# SoM.net
KiCad netlist of a schematic drawn in Altium Designer
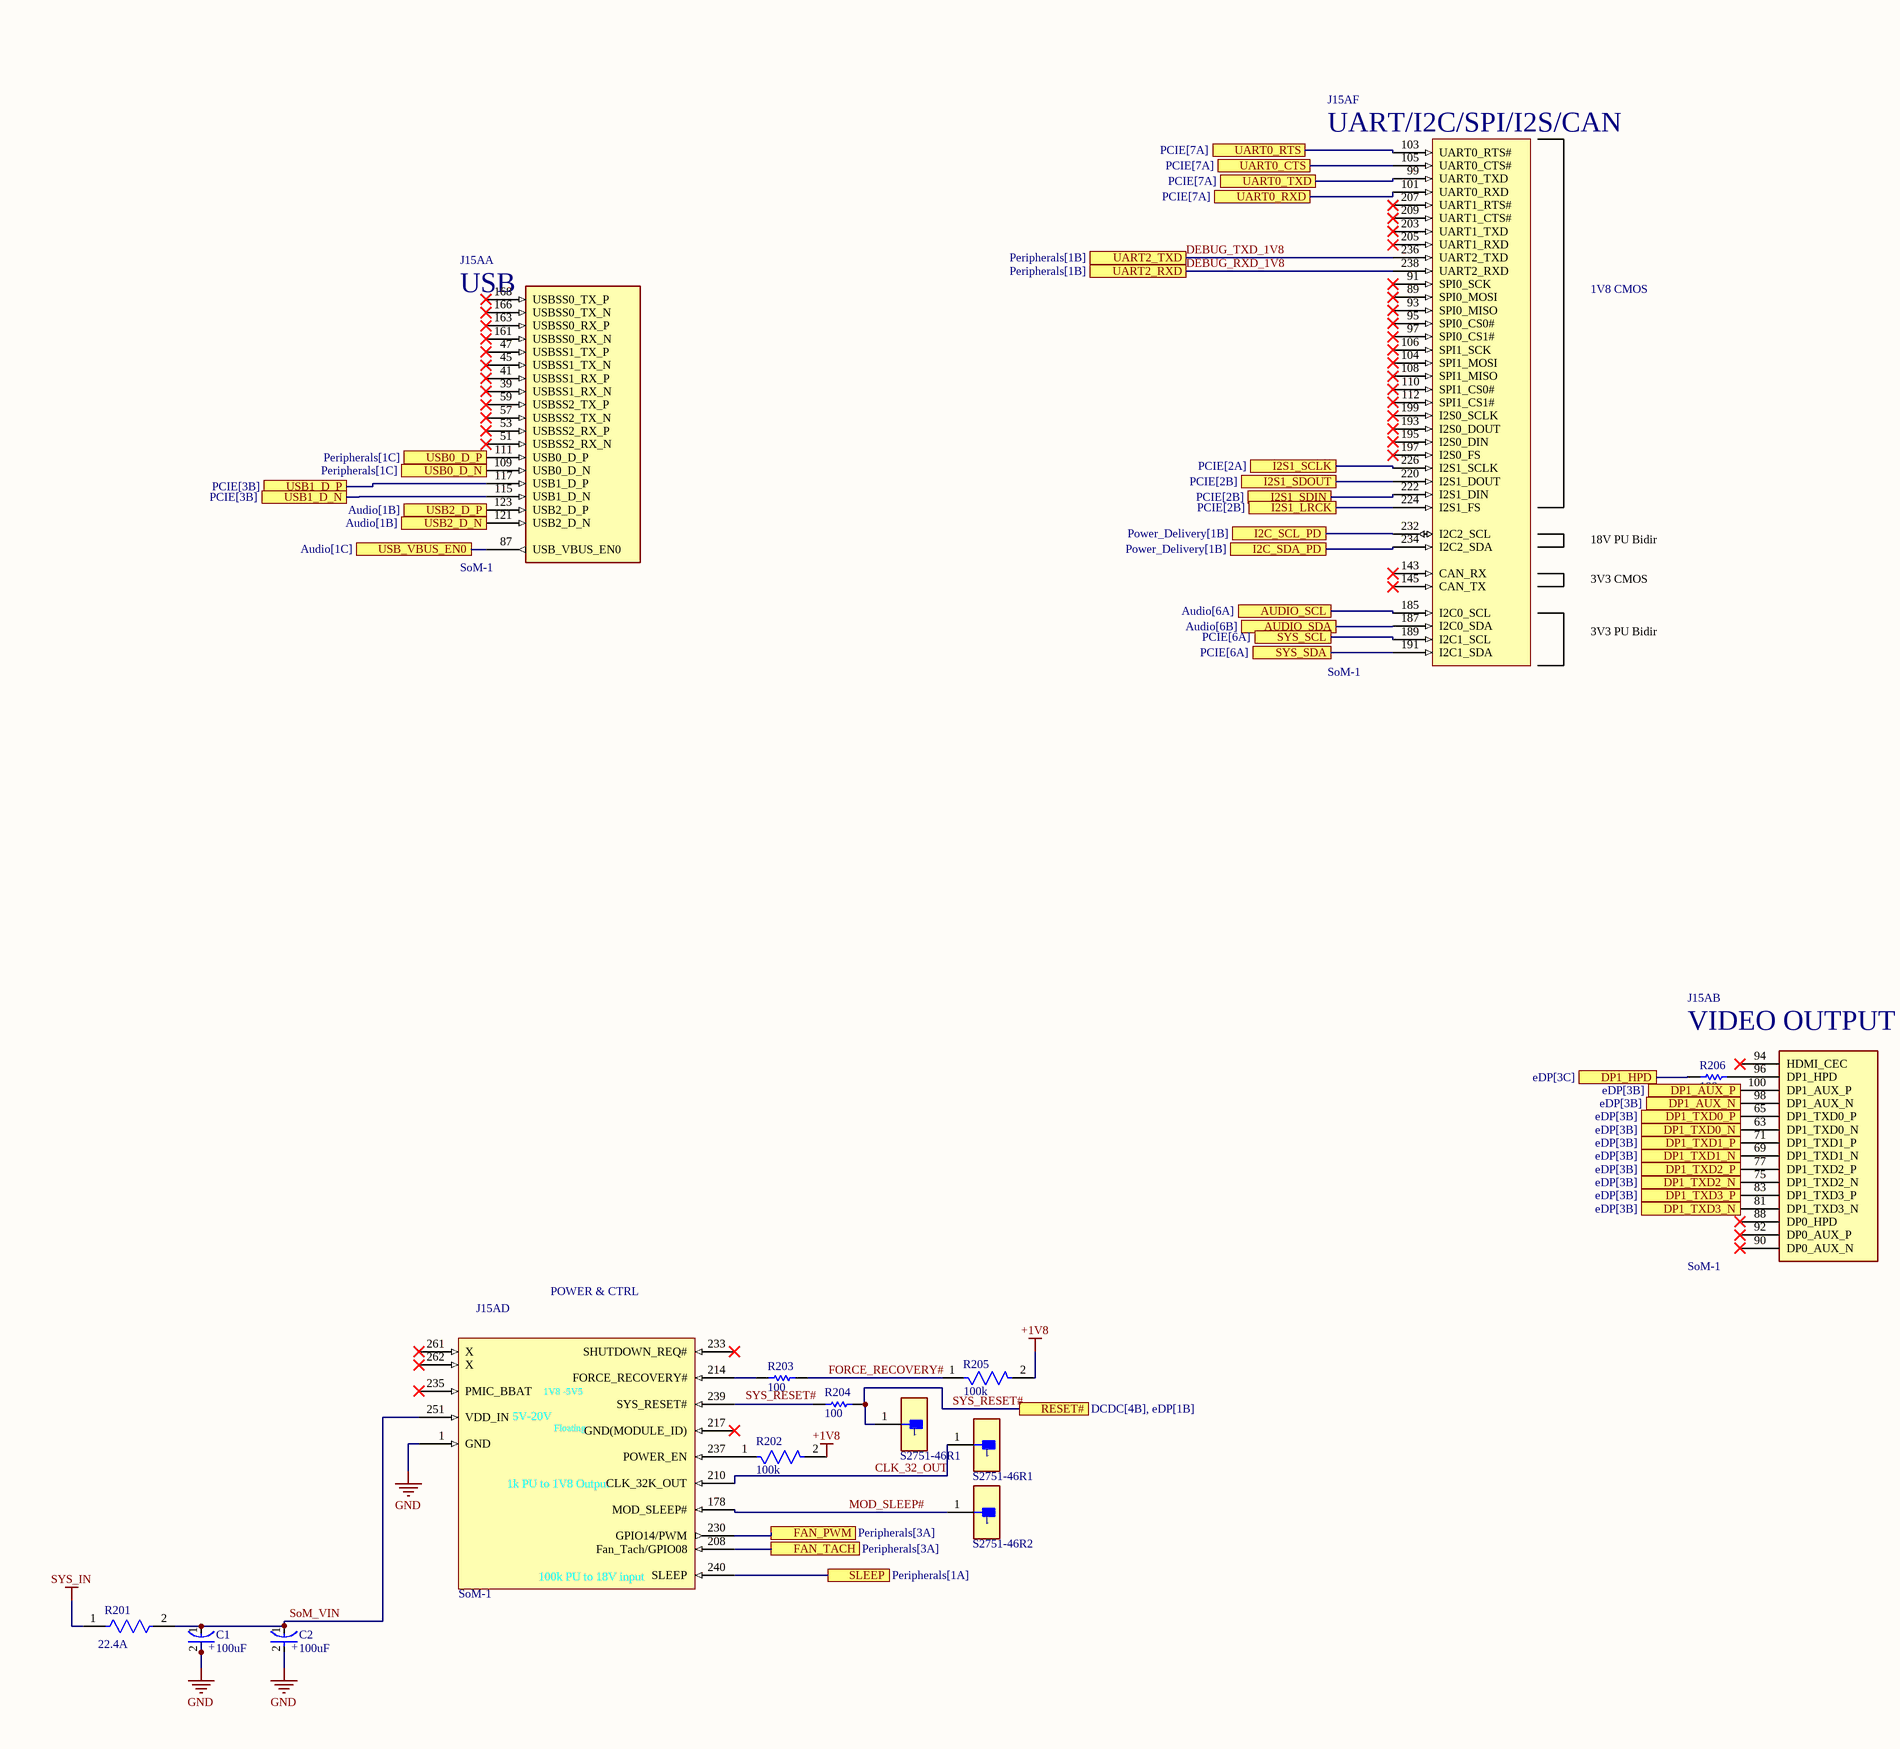
[diagram p0: SoM.SchDoc, left]
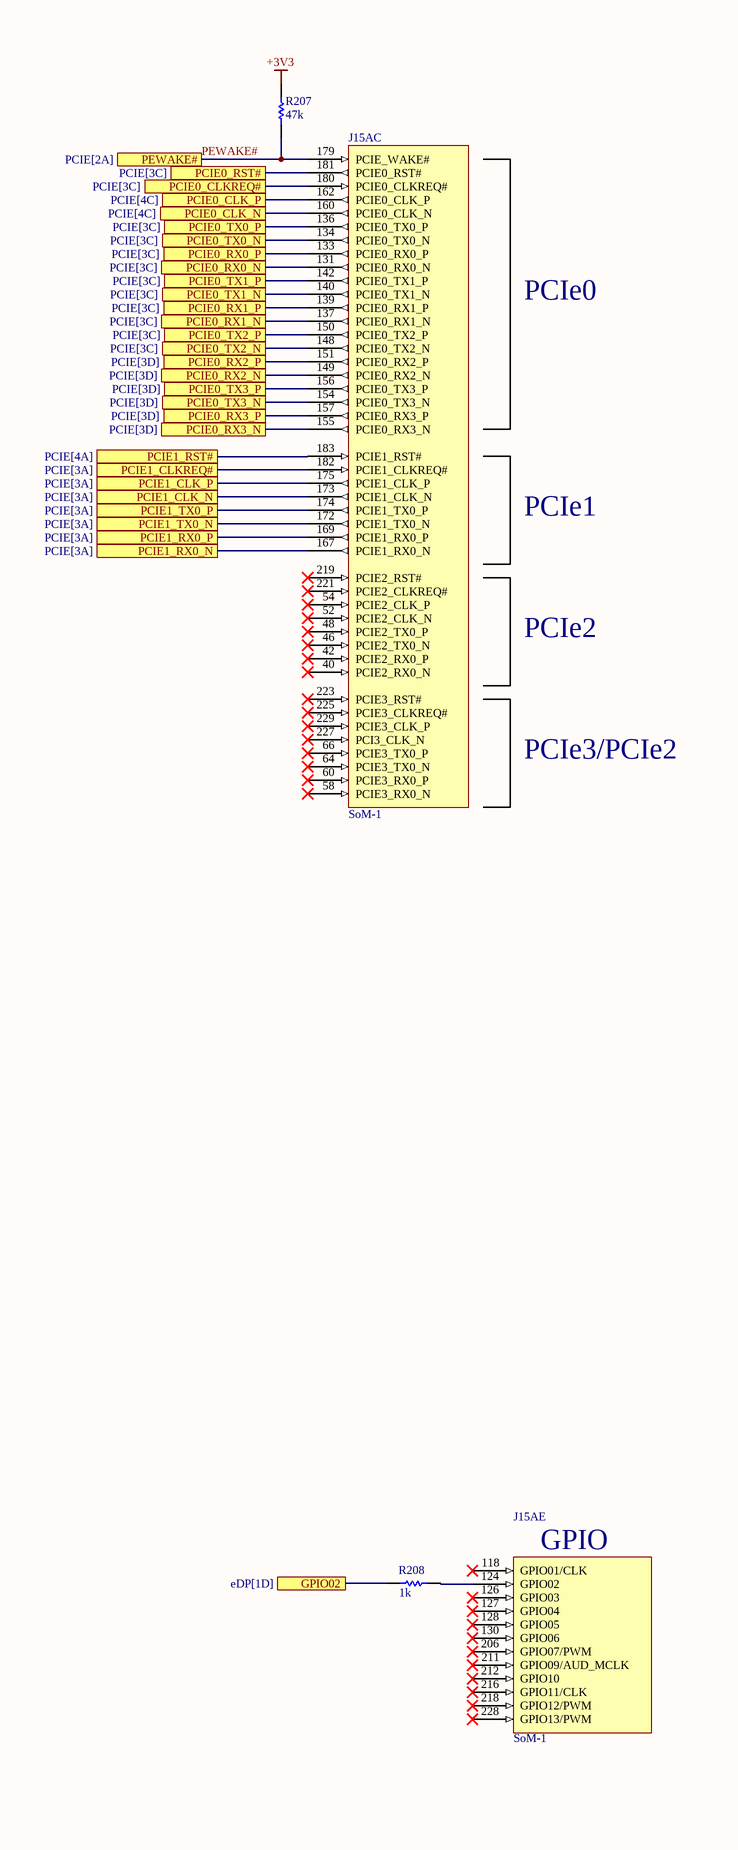
[diagram p1: SoM.SchDoc, right]

(export (version "E")
  (design (tool "Eeschema 10.0.6"))
  (components
    (comp (ref "C1")
      (value "100uF")
      (footprint "FP-T521D107M025ATE040-MFG")
      (description "CAP TANT POLY 100UF 25V 2917")
      (fields (field (name "TOLERANCE") "20%"))
      (libsource (lib "Altium Content Vault") (part "a00bbbee19879c290e62620ae7e47b1"))
    )
    (comp (ref "C2")
      (value "100uF")
      (footprint "FP-T521D107M025ATE040-MFG")
      (description "CAP TANT POLY 100UF 25V 2917")
      (fields (field (name "TOLERANCE") "20%"))
      (libsource (lib "Altium Content Vault") (part "a00bbbee19879c290e62620ae7e47b1"))
    )
    (comp (ref "J15A")
      (value "SoM-1")
      (footprint "FP-2309413-1-MFG")
      (description "Memory Card Connector, DDR4, SODIMM, Cam-In Locking, 260 Contacts, Copper Alloy")
      (fields (field (name "SOURCE") "4d1075b24ee2591bdcd47d674b3d2aa.SchLib"))
      (libsource (lib "Evan") (part "SoM"))
    )
    (comp (ref "J201")
      (value "S2751-46R1")
      (footprint "FP-S2751-46R-MFG")
      (description "PC TEST POINT NATURAL")
      (libsource (lib "Altium Content Vault") (part "dd45045ce8184df9e99e12baf3f412c"))
    )
    (comp (ref "J202")
      (value "S2751-46R1")
      (footprint "FP-S2751-46R-MFG")
      (description "PC TEST POINT NATURAL")
      (libsource (lib "Altium Content Vault") (part "dd45045ce8184df9e99e12baf3f412c"))
    )
    (comp (ref "J203")
      (value "S2751-46R2")
      (footprint "FP-S2751-46R-MFG")
      (description "PC TEST POINT NATURAL")
      (libsource (lib "Altium Content Vault") (part "dd45045ce8184df9e99e12baf3f412c"))
    )
    (comp (ref "R201")
      (value "22.4A")
      (footprint "FP-HCJ0603-MFG")
      (description "RES 0 OHM JUMPER 1/4W 0603")
      (libsource (lib "Altium Content Vault") (part "1029c3af85768c4190bb7ad29bc67b5"))
    )
    (comp (ref "R202")
      (value "100k")
      (footprint "FP-RC0402-0_4-IPC_A")
      (description "RES 100K OHM 5% 1/16W 0402")
      (fields (field (name "TOLERANCE") "5%"))
      (libsource (lib "Altium Content Vault") (part "1029c3af85768c4190bb7ad29bc67b5"))
    )
    (comp (ref "R203")
      (value "100")
      (footprint "RESC1005X40X25ML05T10")
      (fields (field (name "PART NUMBER") "RC0402FR-07100RL") (field (name "MANUFACTURER") "Yageo / Phycomp"))
      (libsource (lib "Altium Content Vault") (part "RES"))
    )
    (comp (ref "R204")
      (value "100")
      (footprint "RESC1005X40X25ML05T10")
      (fields (field (name "PART NUMBER") "RC0402FR-07100RL") (field (name "MANUFACTURER") "Yageo / Phycomp"))
      (libsource (lib "Altium Content Vault") (part "RES"))
    )
    (comp (ref "R205")
      (value "100k")
      (footprint "FP-RC0402-0_4-IPC_A")
      (description "RES 100K OHM 5% 1/16W 0402")
      (fields (field (name "TOLERANCE") "5%"))
      (libsource (lib "Altium Content Vault") (part "1029c3af85768c4190bb7ad29bc67b5"))
    )
    (comp (ref "R206")
      (value "100")
      (footprint "RESC1005X40X25ML05T10")
      (fields (field (name "PART NUMBER") "RC0402FR-07100RL") (field (name "MANUFACTURER") "Yageo / Phycomp"))
      (libsource (lib "Altium Content Vault") (part "RES"))
    )
    (comp (ref "R207")
      (value "47k")
      (footprint "RESC1005X40X25ML05T10")
      (fields (field (name "PART NUMBER") "RC0402FR-0747KL") (field (name "MANUFACTURER") "Yageo / Phycomp"))
      (libsource (lib "Altium Content Vault") (part "RES"))
    )
    (comp (ref "R208")
      (value "1k")
      (footprint "RESC3216X60X45ML15T20")
      (description "Chip Resistor, 1 KOhm, +/- 1%, 0.25 W, -55 to 155 degC, 1206 (3216 Metric), RoHS, Tape and Reel")
      (fields (field (name "MANUFACTURER") "Vishay Semiconductor") (field (name "TOLERANCE") "1%"))
      (libsource (lib "Altium Content Vault") (part "RES-2"))
    )
  )
  (nets
    (net (code "1") (name "+1V8") (class "Default")
      (node (ref "R202") (pin "2") (pinfunction "2_2") (pintype "passive"))
      (node (ref "R205") (pin "2") (pinfunction "2_2") (pintype "passive"))
    )
    (net (code "2") (name "+3V3") (class "Default")
      (node (ref "R207") (pin "2") (pinfunction "2_2") (pintype "passive"))
    )
    (net (code "3") (name "/AUDIO_SCL") (class "Default")
      (node (ref "J15A") (pin "185") (pinfunction "I2C0_SCL_185") (pintype "input"))
    )
    (net (code "4") (name "/AUDIO_SDA") (class "Default")
      (node (ref "J15A") (pin "187") (pinfunction "I2C0_SDA_187") (pintype "input"))
    )
    (net (code "5") (name "/CLK_32_OUT") (class "Default")
      (node (ref "J15A") (pin "210") (pinfunction "CLK_32K_OUT_210") (pintype "input"))
      (node (ref "J202") (pin "1") (pinfunction "1_1") (pintype "passive"))
    )
    (net (code "6") (name "/DEBUG_RXD_1V8") (class "Default")
      (node (ref "J15A") (pin "238") (pinfunction "UART2_RXD_238") (pintype "input"))
    )
    (net (code "7") (name "/DEBUG_TXD_1V8") (class "Default")
      (node (ref "J15A") (pin "236") (pinfunction "UART2_TXD_236") (pintype "input"))
    )
    (net (code "8") (name "/DP1_AUX_N") (class "Default")
      (node (ref "J15A") (pin "98") (pinfunction "DP1_AUX_N_98") (pintype "passive"))
    )
    (net (code "9") (name "/DP1_AUX_P") (class "Default")
      (node (ref "J15A") (pin "100") (pinfunction "DP1_AUX_P_100") (pintype "passive"))
    )
    (net (code "10") (name "/DP1_HPD") (class "Default")
      (node (ref "R206") (pin "1") (pinfunction "1_1") (pintype "passive"))
    )
    (net (code "11") (name "/DP1_TXD0_N") (class "Default")
      (node (ref "J15A") (pin "63") (pinfunction "DP1_TXD0_N_63") (pintype "passive"))
    )
    (net (code "12") (name "/DP1_TXD0_P") (class "Default")
      (node (ref "J15A") (pin "65") (pinfunction "DP1_TXD0_P_65") (pintype "passive"))
    )
    (net (code "13") (name "/DP1_TXD1_N") (class "Default")
      (node (ref "J15A") (pin "69") (pinfunction "DP1_TXD1_N_69") (pintype "passive"))
    )
    (net (code "14") (name "/DP1_TXD1_P") (class "Default")
      (node (ref "J15A") (pin "71") (pinfunction "DP1_TXD1_P_71") (pintype "passive"))
    )
    (net (code "15") (name "/DP1_TXD2_N") (class "Default")
      (node (ref "J15A") (pin "75") (pinfunction "DP1_TXD2_N_75") (pintype "passive"))
    )
    (net (code "16") (name "/DP1_TXD2_P") (class "Default")
      (node (ref "J15A") (pin "77") (pinfunction "DP1_TXD2_P_77") (pintype "passive"))
    )
    (net (code "17") (name "/DP1_TXD3_N") (class "Default")
      (node (ref "J15A") (pin "81") (pinfunction "DP1_TXD3_N_81") (pintype "passive"))
    )
    (net (code "18") (name "/DP1_TXD3_P") (class "Default")
      (node (ref "J15A") (pin "83") (pinfunction "DP1_TXD3_P_83") (pintype "passive"))
    )
    (net (code "19") (name "/FAN_PWM") (class "Default")
      (node (ref "J15A") (pin "230") (pinfunction "GPIO14/PWM_230") (pintype "output"))
    )
    (net (code "20") (name "/FAN_TACH") (class "Default")
      (node (ref "J15A") (pin "208") (pinfunction "Fan_Tach/GPIO08_208") (pintype "input"))
    )
    (net (code "22") (name "/GPIO02") (class "Default")
      (node (ref "R208") (pin "2") (pinfunction "2_2") (pintype "passive"))
    )
    (net (code "23") (name "/I2C_SCL_PD") (class "Default")
      (node (ref "J15A") (pin "232") (pinfunction "I2C2_SCL_232") (pintype "input"))
    )
    (net (code "24") (name "/I2C_SDA_PD") (class "Default")
      (node (ref "J15A") (pin "234") (pinfunction "I2C2_SDA_234") (pintype "input"))
    )
    (net (code "25") (name "/I2S1_LRCK") (class "Default")
      (node (ref "J15A") (pin "224") (pinfunction "I2S1_FS_224") (pintype "input"))
    )
    (net (code "26") (name "/I2S1_SCLK") (class "Default")
      (node (ref "J15A") (pin "226") (pinfunction "I2S1_SCLK_226") (pintype "input"))
    )
    (net (code "27") (name "/I2S1_SDIN") (class "Default")
      (node (ref "J15A") (pin "222") (pinfunction "I2S1_DIN_222") (pintype "input"))
    )
    (net (code "28") (name "/I2S1_SDOUT") (class "Default")
      (node (ref "J15A") (pin "220") (pinfunction "I2S1_DOUT_220") (pintype "input"))
    )
    (net (code "29") (name "/MOD_SLEEP#") (class "Default")
      (node (ref "J15A") (pin "178") (pinfunction "MOD_SLEEP#_178") (pintype "input"))
      (node (ref "J203") (pin "1") (pinfunction "1_1") (pintype "passive"))
    )
    (net (code "30") (name "/PCIE0_CLKREQ#") (class "Default")
      (node (ref "J15A") (pin "180") (pinfunction "PCIE0_CLKREQ#_180") (pintype "input"))
    )
    (net (code "31") (name "/PCIE0_CLK_N") (class "Default")
      (node (ref "J15A") (pin "160") (pinfunction "PCIE0_CLK_N_160") (pintype "input"))
    )
    (net (code "32") (name "/PCIE0_CLK_P") (class "Default")
      (node (ref "J15A") (pin "162") (pinfunction "PCIE0_CLK_P_162") (pintype "input"))
    )
    (net (code "33") (name "/PCIE0_RST#") (class "Default")
      (node (ref "J15A") (pin "181") (pinfunction "PCIE2_CLKREQ#_181") (pintype "input"))
    )
    (net (code "34") (name "/PCIE0_RX0_N") (class "Default")
      (node (ref "J15A") (pin "131") (pinfunction "PCIE0_RX0_N_131") (pintype "input"))
    )
    (net (code "35") (name "/PCIE0_RX0_P") (class "Default")
      (node (ref "J15A") (pin "133") (pinfunction "PCIE0_RX0_P_133") (pintype "input"))
    )
    (net (code "36") (name "/PCIE0_RX1_N") (class "Default")
      (node (ref "J15A") (pin "137") (pinfunction "PCIE0_RX1_N_137") (pintype "input"))
    )
    (net (code "37") (name "/PCIE0_RX1_P") (class "Default")
      (node (ref "J15A") (pin "139") (pinfunction "PCIE0_RX1_P_139") (pintype "input"))
    )
    (net (code "38") (name "/PCIE0_RX2_N") (class "Default")
      (node (ref "J15A") (pin "149") (pinfunction "PCIE0_RX2_N_149") (pintype "input"))
    )
    (net (code "39") (name "/PCIE0_RX2_P") (class "Default")
      (node (ref "J15A") (pin "151") (pinfunction "PCIE0_RX2_P_151") (pintype "input"))
    )
    (net (code "40") (name "/PCIE0_RX3_N") (class "Default")
      (node (ref "J15A") (pin "155") (pinfunction "PCIE0_RX3_N_155") (pintype "input"))
    )
    (net (code "41") (name "/PCIE0_RX3_P") (class "Default")
      (node (ref "J15A") (pin "157") (pinfunction "PCIE0_RX3_P_157") (pintype "input"))
    )
    (net (code "42") (name "/PCIE0_TX0_N") (class "Default")
      (node (ref "J15A") (pin "134") (pinfunction "PCIE0_TX0_N_134") (pintype "input"))
    )
    (net (code "43") (name "/PCIE0_TX0_P") (class "Default")
      (node (ref "J15A") (pin "136") (pinfunction "PCIE0_TX0_P_136") (pintype "input"))
    )
    (net (code "44") (name "/PCIE0_TX1_N") (class "Default")
      (node (ref "J15A") (pin "140") (pinfunction "PCIE0_TX1_N_140") (pintype "input"))
    )
    (net (code "45") (name "/PCIE0_TX1_P") (class "Default")
      (node (ref "J15A") (pin "142") (pinfunction "PCIE0_TX1_P_142") (pintype "input"))
    )
    (net (code "46") (name "/PCIE0_TX2_N") (class "Default")
      (node (ref "J15A") (pin "148") (pinfunction "PCIE0_TX2_N_148") (pintype "input"))
    )
    (net (code "47") (name "/PCIE0_TX2_P") (class "Default")
      (node (ref "J15A") (pin "150") (pinfunction "PCIE0_TX2_P_150") (pintype "input"))
    )
    (net (code "48") (name "/PCIE0_TX3_N") (class "Default")
      (node (ref "J15A") (pin "154") (pinfunction "PCIE0_TX3_P_154") (pintype "input"))
    )
    (net (code "49") (name "/PCIE0_TX3_P") (class "Default")
      (node (ref "J15A") (pin "156") (pinfunction "PCIE0_TX3_P_156") (pintype "input"))
    )
    (net (code "50") (name "/PCIE1_CLKREQ#") (class "Default")
      (node (ref "J15A") (pin "182") (pinfunction "PCIE1_CLKREQ#_182") (pintype "input"))
    )
    (net (code "51") (name "/PCIE1_CLK_N") (class "Default")
      (node (ref "J15A") (pin "173") (pinfunction "PCIE1_CLK_N_173") (pintype "input"))
    )
    (net (code "52") (name "/PCIE1_CLK_P") (class "Default")
      (node (ref "J15A") (pin "175") (pinfunction "PCIE1_CLK_P_175") (pintype "input"))
    )
    (net (code "53") (name "/PCIE1_RST#") (class "Default")
      (node (ref "J15A") (pin "183") (pinfunction "PCIE1_RST#_183") (pintype "input"))
    )
    (net (code "54") (name "/PCIE1_RX0_N") (class "Default")
      (node (ref "J15A") (pin "167") (pinfunction "PCIE1_RX0_N_167") (pintype "input"))
    )
    (net (code "55") (name "/PCIE1_RX0_P") (class "Default")
      (node (ref "J15A") (pin "169") (pinfunction "PCIE1_RX0_P_169") (pintype "input"))
    )
    (net (code "56") (name "/PCIE1_TX0_N") (class "Default")
      (node (ref "J15A") (pin "172") (pinfunction "PCIE1_TX0_N_172") (pintype "input"))
    )
    (net (code "57") (name "/PCIE1_TX0_P") (class "Default")
      (node (ref "J15A") (pin "174") (pinfunction "PCIE1_TX0_P_174") (pintype "input"))
    )
    (net (code "58") (name "/PEWAKE#") (class "Default")
      (node (ref "J15A") (pin "179") (pinfunction "PCIE_WAKE#_179") (pintype "input"))
      (node (ref "R207") (pin "1") (pinfunction "1_1") (pintype "passive"))
    )
    (net (code "59") (name "/SLEEP") (class "Default")
      (node (ref "J15A") (pin "240") (pinfunction "SLEEP_240") (pintype "input"))
    )
    (net (code "60") (name "/SYS_RESET#") (class "Default")
      (node (ref "J201") (pin "1") (pinfunction "1_1") (pintype "passive"))
      (node (ref "R204") (pin "2") (pinfunction "2_2") (pintype "passive"))
    )
    (net (code "61") (name "/SYS_SCL") (class "Default")
      (node (ref "J15A") (pin "189") (pinfunction "IS2C1_SCL_189") (pintype "input"))
    )
    (net (code "62") (name "/SYS_SDA") (class "Default")
      (node (ref "J15A") (pin "191") (pinfunction "IS2C1_SDA_191") (pintype "input"))
    )
    (net (code "63") (name "/SoM_VIN") (class "Default")
      (node (ref "C1") (pin "1") (pinfunction "C_1") (pintype "passive"))
      (node (ref "C2") (pin "1") (pinfunction "C_1") (pintype "passive"))
      (node (ref "J15A") (pin "251") (pinfunction "VDD_IN_251") (pintype "input"))
      (node (ref "R201") (pin "2") (pinfunction "2_2") (pintype "passive"))
    )
    (net (code "64") (name "/UART0_CTS") (class "Default")
      (node (ref "J15A") (pin "105") (pinfunction "UART0_CTS#_105") (pintype "input"))
    )
    (net (code "65") (name "/UART0_RTS") (class "Default")
      (node (ref "J15A") (pin "103") (pinfunction "UART0_RTS#_103") (pintype "input"))
    )
    (net (code "66") (name "/UART0_RXD") (class "Default")
      (node (ref "J15A") (pin "101") (pinfunction "UART0_RXD_101") (pintype "input"))
    )
    (net (code "67") (name "/UART0_TXD") (class "Default")
      (node (ref "J15A") (pin "99") (pinfunction "UART0_TXD_99") (pintype "input"))
    )
    (net (code "68") (name "/USB0_D_N") (class "Default")
      (node (ref "J15A") (pin "109") (pinfunction "USB0_D_N_109") (pintype "input"))
    )
    (net (code "69") (name "/USB0_D_P") (class "Default")
      (node (ref "J15A") (pin "111") (pinfunction "USB0_D_P_111") (pintype "input"))
    )
    (net (code "70") (name "/USB1_D_N") (class "Default")
      (node (ref "J15A") (pin "115") (pinfunction "USB1_D_N_115") (pintype "input"))
    )
    (net (code "71") (name "/USB1_D_P") (class "Default")
      (node (ref "J15A") (pin "117") (pinfunction "USB1_D_P_117") (pintype "input"))
    )
    (net (code "72") (name "/USB2_D_N") (class "Default")
      (node (ref "J15A") (pin "121") (pinfunction "USB2_D_N_121") (pintype "input"))
    )
    (net (code "73") (name "/USB2_D_P") (class "Default")
      (node (ref "J15A") (pin "123") (pinfunction "USB2_D_P_123") (pintype "input"))
    )
    (net (code "74") (name "/USB_VBUS_EN0") (class "Default")
      (node (ref "J15A") (pin "87") (pinfunction "USB_VBUS_EN0_87") (pintype "input"))
    )
    (net (code "75") (name "GND") (class "Default")
      (node (ref "C1") (pin "2") (pinfunction "A_2") (pintype "passive"))
      (node (ref "C2") (pin "2") (pinfunction "A_2") (pintype "passive"))
      (node (ref "J15A") (pin "1") (pinfunction "GND_1") (pintype "input"))
    )
    (net (code "76") (name "Net-(J15AB-DP1_HPD)") (class "Default")
      (node (ref "J15A") (pin "96") (pinfunction "DP1_HPD_96") (pintype "passive"))
      (node (ref "R206") (pin "2") (pinfunction "2_2") (pintype "passive"))
    )
    (net (code "77") (name "Net-(J15AD-FORCE_RECOVERY#)") (class "Default")
      (node (ref "J15A") (pin "214") (pinfunction "FORCE_RECOVERY#_214") (pintype "input"))
      (node (ref "R203") (pin "1") (pinfunction "1_1") (pintype "passive"))
    )
    (net (code "78") (name "Net-(J15AD-POWER_EN)") (class "Default")
      (node (ref "J15A") (pin "237") (pinfunction "POWER_EN_237") (pintype "input"))
      (node (ref "R202") (pin "1") (pinfunction "1_1") (pintype "passive"))
    )
    (net (code "79") (name "Net-(J15AD-SYS_RESET#)") (class "Default")
      (node (ref "J15A") (pin "239") (pinfunction "SYS_RESET#_239") (pintype "input"))
      (node (ref "R204") (pin "1") (pinfunction "1_1") (pintype "passive"))
    )
    (net (code "80") (name "Net-(J15AE-GPIO02)") (class "Default")
      (node (ref "J15A") (pin "124") (pinfunction "GPIO02_124") (pintype "input"))
      (node (ref "R208") (pin "1") (pinfunction "1_1") (pintype "passive"))
    )
    (net (code "81") (name "Net-(R203-Pad2)") (class "Default")
      (node (ref "R203") (pin "2") (pinfunction "2_2") (pintype "passive"))
      (node (ref "R205") (pin "1") (pinfunction "1_1") (pintype "passive"))
    )
    (net (code "82") (name "SYS_IN") (class "Default")
      (node (ref "R201") (pin "1") (pinfunction "1_1") (pintype "passive"))
    )
    (net (code "83") (name "unconnected-(J15AA-USBSS0_RX_N-Pad161)") (class "Default")
      (node (ref "J15A") (pin "161") (pinfunction "USBSS0_RX_N_161") (pintype "input+no_connect"))
    )
    (net (code "84") (name "unconnected-(J15AA-USBSS0_RX_P-Pad163)") (class "Default")
      (node (ref "J15A") (pin "163") (pinfunction "USBSS0_RX_P_163") (pintype "input+no_connect"))
    )
    (net (code "85") (name "unconnected-(J15AA-USBSS0_TX_N-Pad166)") (class "Default")
      (node (ref "J15A") (pin "166") (pinfunction "USBSS0_TX_N_166") (pintype "input+no_connect"))
    )
    (net (code "86") (name "unconnected-(J15AA-USBSS0_TX_P-Pad168)") (class "Default")
      (node (ref "J15A") (pin "168") (pinfunction "USBSS0_TX_P_168") (pintype "input+no_connect"))
    )
    (net (code "87") (name "unconnected-(J15AA-USBSS1_RX_N-Pad39)") (class "Default")
      (node (ref "J15A") (pin "39") (pinfunction "USBSS1_RX_N_39") (pintype "input+no_connect"))
    )
    (net (code "88") (name "unconnected-(J15AA-USBSS1_RX_P-Pad41)") (class "Default")
      (node (ref "J15A") (pin "41") (pinfunction "USBSS1_RX_P_41") (pintype "input+no_connect"))
    )
    (net (code "89") (name "unconnected-(J15AA-USBSS1_TX_N-Pad45)") (class "Default")
      (node (ref "J15A") (pin "45") (pinfunction "USBSS1_TX_N_45") (pintype "input+no_connect"))
    )
    (net (code "90") (name "unconnected-(J15AA-USBSS1_TX_P-Pad47)") (class "Default")
      (node (ref "J15A") (pin "47") (pinfunction "USBSS1_TX_P_47") (pintype "input+no_connect"))
    )
    (net (code "91") (name "unconnected-(J15AA-USBSS2_RX_N-Pad51)") (class "Default")
      (node (ref "J15A") (pin "51") (pinfunction "USBSS2_RX_N_51") (pintype "input+no_connect"))
    )
    (net (code "92") (name "unconnected-(J15AA-USBSS2_RX_P-Pad53)") (class "Default")
      (node (ref "J15A") (pin "53") (pinfunction "USBSS2_RX_P_53") (pintype "input+no_connect"))
    )
    (net (code "93") (name "unconnected-(J15AA-USBSS2_TX_N-Pad57)") (class "Default")
      (node (ref "J15A") (pin "57") (pinfunction "USBSS2_TX_N_57") (pintype "input+no_connect"))
    )
    (net (code "94") (name "unconnected-(J15AA-USBSS2_TX_P-Pad59)") (class "Default")
      (node (ref "J15A") (pin "59") (pinfunction "USBSS2_TX_P_59") (pintype "input+no_connect"))
    )
    (net (code "95") (name "unconnected-(J15AB-DP0_AUX_N-Pad90)") (class "Default")
      (node (ref "J15A") (pin "90") (pinfunction "DP0_AUX_N_90") (pintype "passive+no_connect"))
    )
    (net (code "96") (name "unconnected-(J15AB-DP0_AUX_P-Pad92)") (class "Default")
      (node (ref "J15A") (pin "92") (pinfunction "DP0_AUX_P_92") (pintype "passive+no_connect"))
    )
    (net (code "97") (name "unconnected-(J15AB-DP0_HPD-Pad88)") (class "Default")
      (node (ref "J15A") (pin "88") (pinfunction "DP0_HPD_88") (pintype "passive+no_connect"))
    )
    (net (code "98") (name "unconnected-(J15AB-HDMI_CEC-Pad94)") (class "Default")
      (node (ref "J15A") (pin "94") (pinfunction "HDMI_CEC_94") (pintype "passive+no_connect"))
    )
    (net (code "99") (name "unconnected-(J15AC-PCI3_CLK_N-Pad227)") (class "Default")
      (node (ref "J15A") (pin "227") (pinfunction "PCI3_CLK_N_227") (pintype "input+no_connect"))
    )
    (net (code "100") (name "unconnected-(J15AC-PCIE2_CLKREQ#-Pad221)") (class "Default")
      (node (ref "J15A") (pin "221") (pinfunction "PCIE2_CLKREQ#_221") (pintype "input+no_connect"))
    )
    (net (code "101") (name "unconnected-(J15AC-PCIE2_CLK_N-Pad52)") (class "Default")
      (node (ref "J15A") (pin "52") (pinfunction "PCIE2_CLK_N_52") (pintype "input+no_connect"))
    )
    (net (code "102") (name "unconnected-(J15AC-PCIE2_CLK_P-Pad54)") (class "Default")
      (node (ref "J15A") (pin "54") (pinfunction "PCIE2_CLK_P_54") (pintype "input+no_connect"))
    )
    (net (code "103") (name "unconnected-(J15AC-PCIE2_RST#-Pad219)") (class "Default")
      (node (ref "J15A") (pin "219") (pinfunction "PCIE2_RST#_219") (pintype "input+no_connect"))
    )
    (net (code "104") (name "unconnected-(J15AC-PCIE2_RX0_N-Pad40)") (class "Default")
      (node (ref "J15A") (pin "40") (pinfunction "PCIE2_RX0_N_40") (pintype "input+no_connect"))
    )
    (net (code "105") (name "unconnected-(J15AC-PCIE2_RX0_P-Pad42)") (class "Default")
      (node (ref "J15A") (pin "42") (pinfunction "PCIE2_RX0_P_42") (pintype "input+no_connect"))
    )
    (net (code "106") (name "unconnected-(J15AC-PCIE2_TX0_N-Pad46)") (class "Default")
      (node (ref "J15A") (pin "46") (pinfunction "PCIE2_TX0_N_46") (pintype "input+no_connect"))
    )
    (net (code "107") (name "unconnected-(J15AC-PCIE2_TX0_P-Pad48)") (class "Default")
      (node (ref "J15A") (pin "48") (pinfunction "PCIE2_TX0_P_48") (pintype "input+no_connect"))
    )
    (net (code "108") (name "unconnected-(J15AC-PCIE3_CLKREQ#-Pad225)") (class "Default")
      (node (ref "J15A") (pin "225") (pinfunction "PCIE3_CLKREQ#_225") (pintype "input+no_connect"))
    )
    (net (code "109") (name "unconnected-(J15AC-PCIE3_CLK_P-Pad229)") (class "Default")
      (node (ref "J15A") (pin "229") (pinfunction "PCIE3_CLK_P_229") (pintype "input+no_connect"))
    )
    (net (code "110") (name "unconnected-(J15AC-PCIE3_RST#-Pad223)") (class "Default")
      (node (ref "J15A") (pin "223") (pinfunction "PCIE3_RST#_223") (pintype "input+no_connect"))
    )
    (net (code "111") (name "unconnected-(J15AC-PCIE3_RX0_N-Pad58)") (class "Default")
      (node (ref "J15A") (pin "58") (pinfunction "PCIE3_RX0_N_58") (pintype "input+no_connect"))
    )
    (net (code "112") (name "unconnected-(J15AC-PCIE3_RX0_P-Pad60)") (class "Default")
      (node (ref "J15A") (pin "60") (pinfunction "PCIE3_RX0_P_60") (pintype "input+no_connect"))
    )
    (net (code "113") (name "unconnected-(J15AC-PCIE3_TX0_N-Pad64)") (class "Default")
      (node (ref "J15A") (pin "64") (pinfunction "PCIE3_TX0_N_64") (pintype "input+no_connect"))
    )
    (net (code "114") (name "unconnected-(J15AC-PCIE3_TX0_P-Pad66)") (class "Default")
      (node (ref "J15A") (pin "66") (pinfunction "PCIE3_TX0_P_66") (pintype "input+no_connect"))
    )
    (net (code "115") (name "unconnected-(J15AD-GND(MODULE_ID)-Pad217)") (class "Default")
      (node (ref "J15A") (pin "217") (pinfunction "GND(MODULE_ID)_217") (pintype "input+no_connect"))
    )
    (net (code "116") (name "unconnected-(J15AD-PMIC_BBAT-Pad235)") (class "Default")
      (node (ref "J15A") (pin "235") (pinfunction "PMIC_BBAT_235") (pintype "input+no_connect"))
    )
    (net (code "117") (name "unconnected-(J15AD-SHUTDOWN_REQ#-Pad233)") (class "Default")
      (node (ref "J15A") (pin "233") (pinfunction "SHUTDOWN_REQ#_233") (pintype "input+no_connect"))
    )
    (net (code "118") (name "unconnected-(J15AD-X-Pad261)") (class "Default")
      (node (ref "J15A") (pin "261") (pinfunction "X_261") (pintype "input+no_connect"))
    )
    (net (code "119") (name "unconnected-(J15AD-X-Pad262)") (class "Default")
      (node (ref "J15A") (pin "262") (pinfunction "X_262") (pintype "input+no_connect"))
    )
    (net (code "120") (name "unconnected-(J15AE-GPIO01{slash}CLK-Pad118)") (class "Default")
      (node (ref "J15A") (pin "118") (pinfunction "GPIO01/CLK_118") (pintype "input+no_connect"))
    )
    (net (code "121") (name "unconnected-(J15AE-GPIO03-Pad126)") (class "Default")
      (node (ref "J15A") (pin "126") (pinfunction "GPIO03_126") (pintype "input+no_connect"))
    )
    (net (code "122") (name "unconnected-(J15AE-GPIO04-Pad127)") (class "Default")
      (node (ref "J15A") (pin "127") (pinfunction "GPIO04_127") (pintype "input+no_connect"))
    )
    (net (code "123") (name "unconnected-(J15AE-GPIO05-Pad128)") (class "Default")
      (node (ref "J15A") (pin "128") (pinfunction "GPIO05_128") (pintype "input+no_connect"))
    )
    (net (code "124") (name "unconnected-(J15AE-GPIO06-Pad130)") (class "Default")
      (node (ref "J15A") (pin "130") (pinfunction "GPIO06_130") (pintype "input+no_connect"))
    )
    (net (code "125") (name "unconnected-(J15AE-GPIO07{slash}PWM-Pad206)") (class "Default")
      (node (ref "J15A") (pin "206") (pinfunction "GPIO07/PWM_206") (pintype "input+no_connect"))
    )
    (net (code "126") (name "unconnected-(J15AE-GPIO09{slash}AUD_MCLK-Pad211)") (class "Default")
      (node (ref "J15A") (pin "211") (pinfunction "GPIO09/AUD_MCLK_211") (pintype "input+no_connect"))
    )
    (net (code "127") (name "unconnected-(J15AE-GPIO10-Pad212)") (class "Default")
      (node (ref "J15A") (pin "212") (pinfunction "GPIO10_212") (pintype "input+no_connect"))
    )
    (net (code "128") (name "unconnected-(J15AE-GPIO11{slash}CLK-Pad216)") (class "Default")
      (node (ref "J15A") (pin "216") (pinfunction "GPIO11/CLK_216") (pintype "input+no_connect"))
    )
    (net (code "129") (name "unconnected-(J15AE-GPIO12{slash}PWM-Pad218)") (class "Default")
      (node (ref "J15A") (pin "218") (pinfunction "GPIO12/PWM_218") (pintype "input+no_connect"))
    )
    (net (code "130") (name "unconnected-(J15AE-GPIO13{slash}PWM-Pad228)") (class "Default")
      (node (ref "J15A") (pin "228") (pinfunction "GPIO13/PWM_228") (pintype "input+no_connect"))
    )
    (net (code "131") (name "unconnected-(J15AF-CAN_RX-Pad143)") (class "Default")
      (node (ref "J15A") (pin "143") (pinfunction "CAN_RX_143") (pintype "input+no_connect"))
    )
    (net (code "132") (name "unconnected-(J15AF-CAN_TX-Pad145)") (class "Default")
      (node (ref "J15A") (pin "145") (pinfunction "CAN_TX_145") (pintype "input+no_connect"))
    )
    (net (code "133") (name "unconnected-(J15AF-I2S0_DIN-Pad195)") (class "Default")
      (node (ref "J15A") (pin "195") (pinfunction "I2S0_DIN_195") (pintype "input+no_connect"))
    )
    (net (code "134") (name "unconnected-(J15AF-I2S0_DOUT-Pad193)") (class "Default")
      (node (ref "J15A") (pin "193") (pinfunction "I2S0_DOUT_193") (pintype "input+no_connect"))
    )
    (net (code "135") (name "unconnected-(J15AF-I2S0_FS-Pad197)") (class "Default")
      (node (ref "J15A") (pin "197") (pinfunction "I2S0_FS_197") (pintype "input+no_connect"))
    )
    (net (code "136") (name "unconnected-(J15AF-I2S0_SCLK-Pad199)") (class "Default")
      (node (ref "J15A") (pin "199") (pinfunction "I2S0_SCLK_199") (pintype "input+no_connect"))
    )
    (net (code "137") (name "unconnected-(J15AF-SPI0_CS0#-Pad95)") (class "Default")
      (node (ref "J15A") (pin "95") (pinfunction "SPI0_CS0#_95") (pintype "input+no_connect"))
    )
    (net (code "138") (name "unconnected-(J15AF-SPI0_CS1#-Pad97)") (class "Default")
      (node (ref "J15A") (pin "97") (pinfunction "SPI0_CS1#_97") (pintype "input+no_connect"))
    )
    (net (code "139") (name "unconnected-(J15AF-SPI0_MISO-Pad93)") (class "Default")
      (node (ref "J15A") (pin "93") (pinfunction "SPI0_MISO_93") (pintype "input+no_connect"))
    )
    (net (code "140") (name "unconnected-(J15AF-SPI0_MOSI-Pad89)") (class "Default")
      (node (ref "J15A") (pin "89") (pinfunction "SPI0_MOSI_89") (pintype "input+no_connect"))
    )
    (net (code "141") (name "unconnected-(J15AF-SPI0_SCK-Pad91)") (class "Default")
      (node (ref "J15A") (pin "91") (pinfunction "SPI0_SCK_91") (pintype "input+no_connect"))
    )
    (net (code "142") (name "unconnected-(J15AF-SPI1_CS0#-Pad110)") (class "Default")
      (node (ref "J15A") (pin "110") (pinfunction "SPI1_CS0#_110") (pintype "input+no_connect"))
    )
    (net (code "143") (name "unconnected-(J15AF-SPI1_CS1#-Pad112)") (class "Default")
      (node (ref "J15A") (pin "112") (pinfunction "SPI1_CS1#_112") (pintype "input+no_connect"))
    )
    (net (code "144") (name "unconnected-(J15AF-SPI1_MISO-Pad108)") (class "Default")
      (node (ref "J15A") (pin "108") (pinfunction "SPI1_MISO_108") (pintype "input+no_connect"))
    )
    (net (code "145") (name "unconnected-(J15AF-SPI1_MOSI-Pad104)") (class "Default")
      (node (ref "J15A") (pin "104") (pinfunction "SPI1_MOSI_104") (pintype "input+no_connect"))
    )
    (net (code "146") (name "unconnected-(J15AF-SPI1_SCK-Pad106)") (class "Default")
      (node (ref "J15A") (pin "106") (pinfunction "SPI1_SCK_106") (pintype "input+no_connect"))
    )
    (net (code "147") (name "unconnected-(J15AF-UART1_CTS#-Pad209)") (class "Default")
      (node (ref "J15A") (pin "209") (pinfunction "UART1_CTS#_209") (pintype "input+no_connect"))
    )
    (net (code "148") (name "unconnected-(J15AF-UART1_RTS#-Pad207)") (class "Default")
      (node (ref "J15A") (pin "207") (pinfunction "UART1_RTS#_207") (pintype "input+no_connect"))
    )
    (net (code "149") (name "unconnected-(J15AF-UART1_RXD-Pad205)") (class "Default")
      (node (ref "J15A") (pin "205") (pinfunction "UART1_RXD_205") (pintype "input+no_connect"))
    )
    (net (code "150") (name "unconnected-(J15AF-UART1_TXD-Pad203)") (class "Default")
      (node (ref "J15A") (pin "203") (pinfunction "UART1_TXD_203") (pintype "input+no_connect"))
    )
  )
)
